# Power_Strip.net
KiCad netlist of a schematic drawn in EAGLE
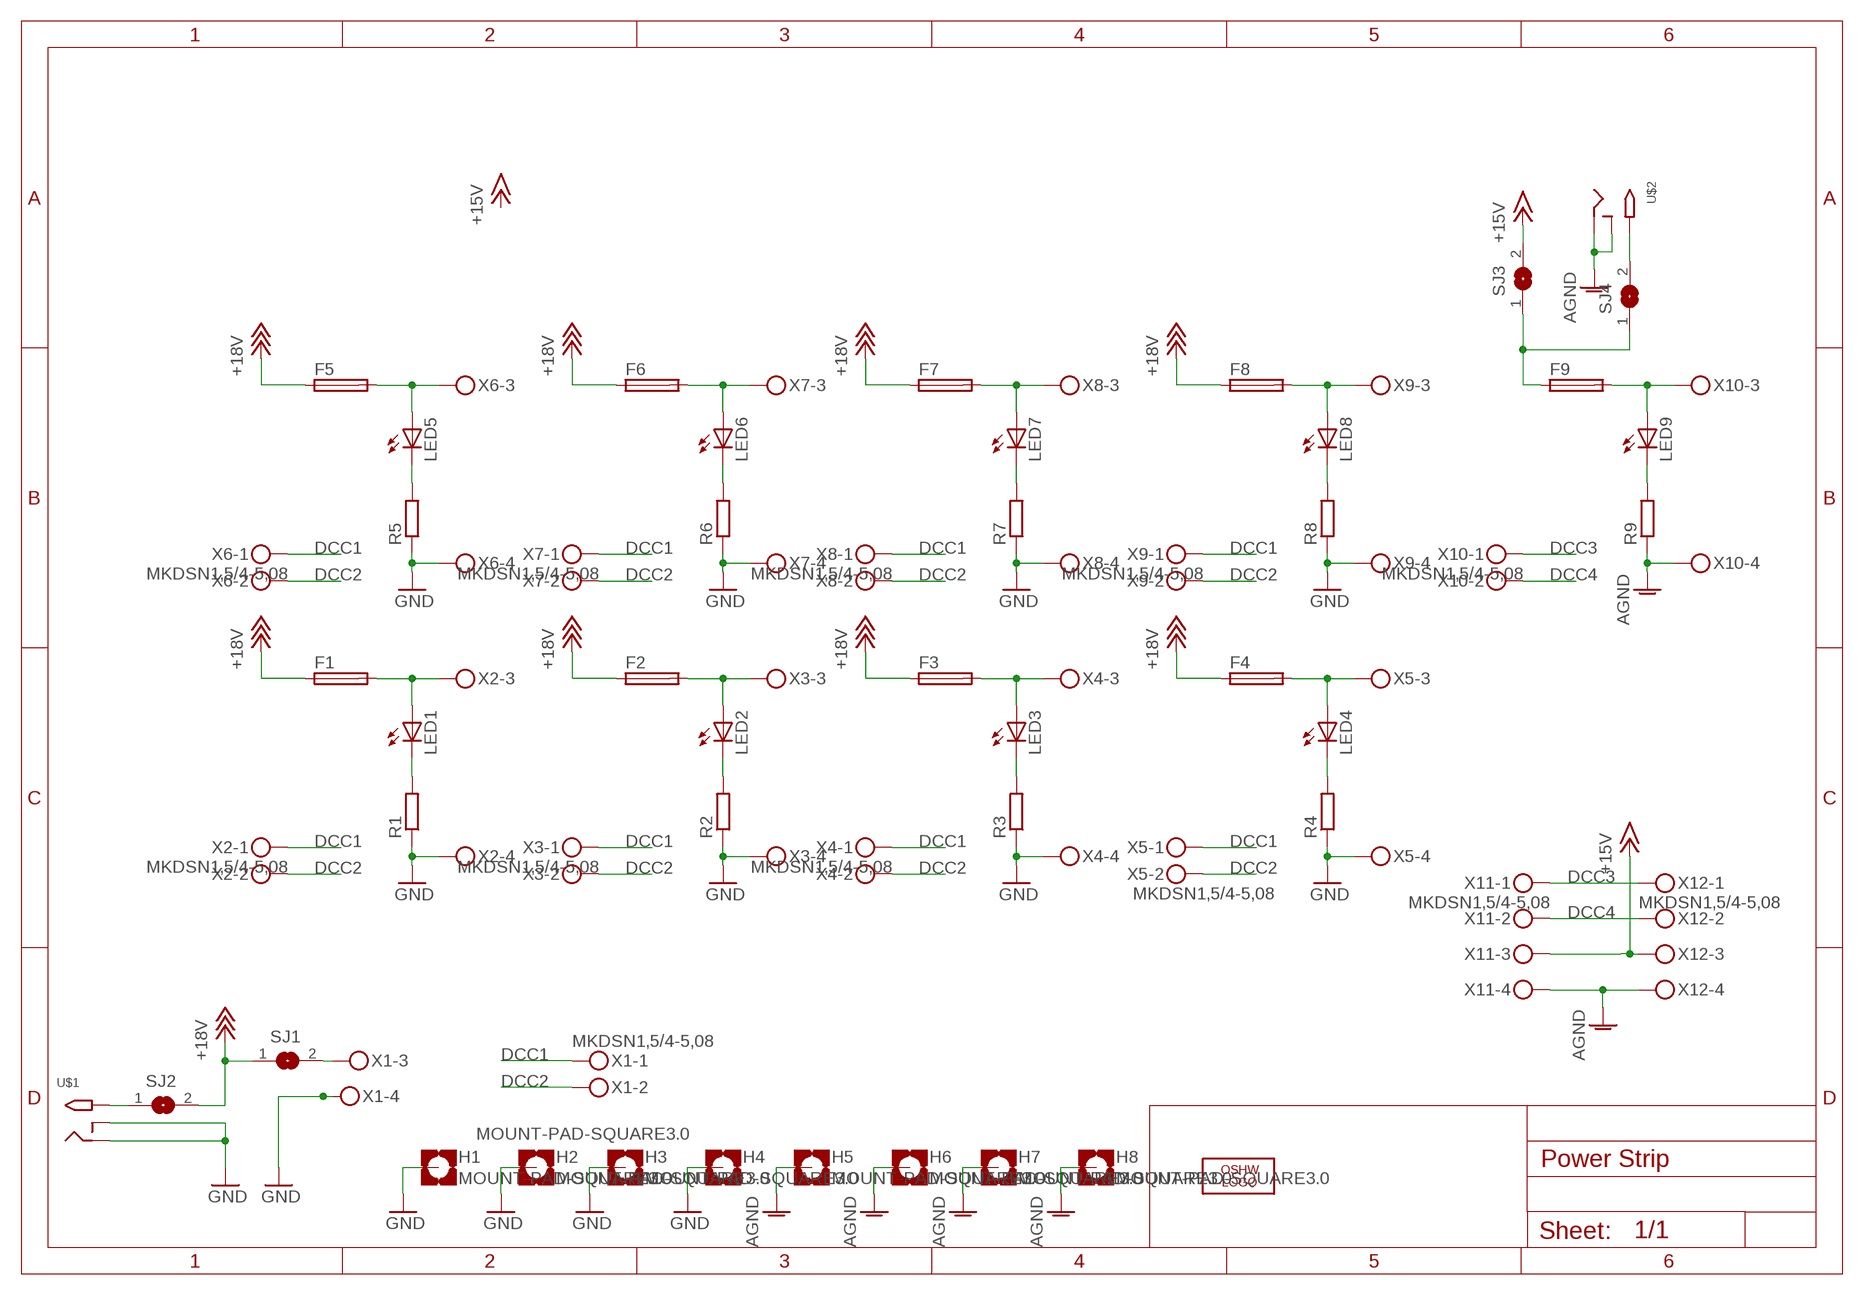
[diagram p0: schematic, sheet 1]

(export (version "E")
  (design (tool "Eeschema 10.0.6"))
  (components
    (comp (ref "F1")
      (value "TE5")
      (footprint "eagle-import:TE5")
      (libsource (lib "eagle-import") (part "TE5"))
    )
    (comp (ref "F2")
      (value "TE5")
      (footprint "eagle-import:TE5")
      (libsource (lib "eagle-import") (part "TE5"))
    )
    (comp (ref "F3")
      (value "TE5")
      (footprint "eagle-import:TE5")
      (libsource (lib "eagle-import") (part "TE5"))
    )
    (comp (ref "F4")
      (value "TE5")
      (footprint "eagle-import:TE5")
      (libsource (lib "eagle-import") (part "TE5"))
    )
    (comp (ref "F5")
      (value "TE5")
      (footprint "eagle-import:TE5")
      (libsource (lib "eagle-import") (part "TE5"))
    )
    (comp (ref "F6")
      (value "TE5")
      (footprint "eagle-import:TE5")
      (libsource (lib "eagle-import") (part "TE5"))
    )
    (comp (ref "F7")
      (value "TE5")
      (footprint "eagle-import:TE5")
      (libsource (lib "eagle-import") (part "TE5"))
    )
    (comp (ref "F8")
      (value "TE5")
      (footprint "eagle-import:TE5")
      (libsource (lib "eagle-import") (part "TE5"))
    )
    (comp (ref "F9")
      (value "TE5")
      (footprint "eagle-import:TE5")
      (libsource (lib "eagle-import") (part "TE5"))
    )
    (comp (ref "H1")
      (value "MOUNT-PAD-SQUARE3.0")
      (footprint "eagle-import:3,0-PAD-SQUARE")
      (libsource (lib "eagle-import") (part "MOUNT-PAD-SQUARE3.0"))
    )
    (comp (ref "H2")
      (value "MOUNT-PAD-SQUARE3.0")
      (footprint "eagle-import:3,0-PAD-SQUARE")
      (libsource (lib "eagle-import") (part "MOUNT-PAD-SQUARE3.0"))
    )
    (comp (ref "H3")
      (value "MOUNT-PAD-SQUARE3.0")
      (footprint "eagle-import:3,0-PAD-SQUARE")
      (libsource (lib "eagle-import") (part "MOUNT-PAD-SQUARE3.0"))
    )
    (comp (ref "H4")
      (value "MOUNT-PAD-SQUARE3.0")
      (footprint "eagle-import:3,0-PAD-SQUARE")
      (libsource (lib "eagle-import") (part "MOUNT-PAD-SQUARE3.0"))
    )
    (comp (ref "H5")
      (value "MOUNT-PAD-SQUARE3.0")
      (footprint "eagle-import:3,0-PAD-SQUARE")
      (libsource (lib "eagle-import") (part "MOUNT-PAD-SQUARE3.0"))
    )
    (comp (ref "H6")
      (value "MOUNT-PAD-SQUARE3.0")
      (footprint "eagle-import:3,0-PAD-SQUARE")
      (libsource (lib "eagle-import") (part "MOUNT-PAD-SQUARE3.0"))
    )
    (comp (ref "H7")
      (value "MOUNT-PAD-SQUARE3.0")
      (footprint "eagle-import:3,0-PAD-SQUARE")
      (libsource (lib "eagle-import") (part "MOUNT-PAD-SQUARE3.0"))
    )
    (comp (ref "H8")
      (value "MOUNT-PAD-SQUARE3.0")
      (footprint "eagle-import:3,0-PAD-SQUARE")
      (libsource (lib "eagle-import") (part "MOUNT-PAD-SQUARE3.0"))
    )
    (comp (ref "LED1")
      (value "LED3MM")
      (footprint "eagle-import:LED3MM")
      (libsource (lib "eagle-import") (part "LED3MM"))
    )
    (comp (ref "LED2")
      (value "LED3MM")
      (footprint "eagle-import:LED3MM")
      (libsource (lib "eagle-import") (part "LED3MM"))
    )
    (comp (ref "LED3")
      (value "LED3MM")
      (footprint "eagle-import:LED3MM")
      (libsource (lib "eagle-import") (part "LED3MM"))
    )
    (comp (ref "LED4")
      (value "LED3MM")
      (footprint "eagle-import:LED3MM")
      (libsource (lib "eagle-import") (part "LED3MM"))
    )
    (comp (ref "LED5")
      (value "LED3MM")
      (footprint "eagle-import:LED3MM")
      (libsource (lib "eagle-import") (part "LED3MM"))
    )
    (comp (ref "LED6")
      (value "LED3MM")
      (footprint "eagle-import:LED3MM")
      (libsource (lib "eagle-import") (part "LED3MM"))
    )
    (comp (ref "LED7")
      (value "LED3MM")
      (footprint "eagle-import:LED3MM")
      (libsource (lib "eagle-import") (part "LED3MM"))
    )
    (comp (ref "LED8")
      (value "LED3MM")
      (footprint "eagle-import:LED3MM")
      (libsource (lib "eagle-import") (part "LED3MM"))
    )
    (comp (ref "LED9")
      (value "LED3MM")
      (footprint "eagle-import:LED3MM")
      (libsource (lib "eagle-import") (part "LED3MM"))
    )
    (comp (ref "LOGO1")
      (value "OSHW_LOGO_6MILX0200-NT")
      (footprint "eagle-import:OSHW_6X200_NOTEXT")
      (libsource (lib "eagle-import") (part "OSHW_LOGO_6MILX0200-NT"))
    )
    (comp (ref "R1")
      (value "R-EU_R0805")
      (footprint "eagle-import:R0805")
      (libsource (lib "eagle-import") (part "R-EU_R0805"))
    )
    (comp (ref "R2")
      (value "R-EU_R0805")
      (footprint "eagle-import:R0805")
      (libsource (lib "eagle-import") (part "R-EU_R0805"))
    )
    (comp (ref "R3")
      (value "R-EU_R0805")
      (footprint "eagle-import:R0805")
      (libsource (lib "eagle-import") (part "R-EU_R0805"))
    )
    (comp (ref "R4")
      (value "R-EU_R0805")
      (footprint "eagle-import:R0805")
      (libsource (lib "eagle-import") (part "R-EU_R0805"))
    )
    (comp (ref "R5")
      (value "R-EU_R0805")
      (footprint "eagle-import:R0805")
      (libsource (lib "eagle-import") (part "R-EU_R0805"))
    )
    (comp (ref "R6")
      (value "R-EU_R0805")
      (footprint "eagle-import:R0805")
      (libsource (lib "eagle-import") (part "R-EU_R0805"))
    )
    (comp (ref "R7")
      (value "R-EU_R0805")
      (footprint "eagle-import:R0805")
      (libsource (lib "eagle-import") (part "R-EU_R0805"))
    )
    (comp (ref "R8")
      (value "R-EU_R0805")
      (footprint "eagle-import:R0805")
      (libsource (lib "eagle-import") (part "R-EU_R0805"))
    )
    (comp (ref "R9")
      (value "R-EU_R0805")
      (footprint "eagle-import:R0805")
      (libsource (lib "eagle-import") (part "R-EU_R0805"))
    )
    (comp (ref "SJ1") (value "SJ") (footprint "eagle-import:SJ") (libsource (lib "eagle-import") (part "SJ")))
    (comp (ref "SJ2") (value "SJ") (footprint "eagle-import:SJ") (libsource (lib "eagle-import") (part "SJ")))
    (comp (ref "SJ3") (value "SJ") (footprint "eagle-import:SJ") (libsource (lib "eagle-import") (part "SJ")))
    (comp (ref "SJ4") (value "SJ") (footprint "eagle-import:SJ") (libsource (lib "eagle-import") (part "SJ")))
    (comp (ref "U$1")
      (value "2.1MMJACKTHM")
      (footprint "eagle-import:PJ-102A")
      (libsource (lib "eagle-import") (part "2.1MMJACKTHM"))
    )
    (comp (ref "U$2")
      (value "2.1MMJACKTHM")
      (footprint "eagle-import:PJ-102A")
      (libsource (lib "eagle-import") (part "2.1MMJACKTHM"))
    )
    (comp (ref "X1")
      (value "MKDSN1,5/4-5,08")
      (footprint "eagle-import:MKDSN1,5_4-5,08")
      (libsource (lib "eagle-import") (part "MKDSN1,5/4-5,08"))
    )
    (comp (ref "X2")
      (value "MKDSN1,5/4-5,08")
      (footprint "eagle-import:MKDSN1,5_4-5,08")
      (libsource (lib "eagle-import") (part "MKDSN1,5/4-5,08"))
    )
    (comp (ref "X3")
      (value "MKDSN1,5/4-5,08")
      (footprint "eagle-import:MKDSN1,5_4-5,08")
      (libsource (lib "eagle-import") (part "MKDSN1,5/4-5,08"))
    )
    (comp (ref "X4")
      (value "MKDSN1,5/4-5,08")
      (footprint "eagle-import:MKDSN1,5_4-5,08")
      (libsource (lib "eagle-import") (part "MKDSN1,5/4-5,08"))
    )
    (comp (ref "X5")
      (value "MKDSN1,5/4-5,08")
      (footprint "eagle-import:MKDSN1,5_4-5,08")
      (libsource (lib "eagle-import") (part "MKDSN1,5/4-5,08"))
    )
    (comp (ref "X6")
      (value "MKDSN1,5/4-5,08")
      (footprint "eagle-import:MKDSN1,5_4-5,08")
      (libsource (lib "eagle-import") (part "MKDSN1,5/4-5,08"))
    )
    (comp (ref "X7")
      (value "MKDSN1,5/4-5,08")
      (footprint "eagle-import:MKDSN1,5_4-5,08")
      (libsource (lib "eagle-import") (part "MKDSN1,5/4-5,08"))
    )
    (comp (ref "X8")
      (value "MKDSN1,5/4-5,08")
      (footprint "eagle-import:MKDSN1,5_4-5,08")
      (libsource (lib "eagle-import") (part "MKDSN1,5/4-5,08"))
    )
    (comp (ref "X9")
      (value "MKDSN1,5/4-5,08")
      (footprint "eagle-import:MKDSN1,5_4-5,08")
      (libsource (lib "eagle-import") (part "MKDSN1,5/4-5,08"))
    )
    (comp (ref "X10")
      (value "MKDSN1,5/4-5,08")
      (footprint "eagle-import:MKDSN1,5_4-5,08")
      (libsource (lib "eagle-import") (part "MKDSN1,5/4-5,08"))
    )
    (comp (ref "X11")
      (value "MKDSN1,5/4-5,08")
      (footprint "eagle-import:MKDSN1,5_4-5,08")
      (libsource (lib "eagle-import") (part "MKDSN1,5/4-5,08"))
    )
    (comp (ref "X12")
      (value "MKDSN1,5/4-5,08")
      (footprint "eagle-import:MKDSN1,5_4-5,08")
      (libsource (lib "eagle-import") (part "MKDSN1,5/4-5,08"))
    )
  )
  (nets
    (net (code "1") (name "+15V") (class "Default")
      (node (ref "SJ3") (pin "2") (pinfunction "2_2") (pintype "passive"))
      (node (ref "X11") (pin "3") (pinfunction "KL_3") (pintype "passive"))
      (node (ref "X12") (pin "3") (pinfunction "KL_3") (pintype "passive"))
    )
    (net (code "2") (name "+18V") (class "Default")
      (node (ref "F1") (pin "1") (pinfunction "1_1") (pintype "passive"))
      (node (ref "F2") (pin "1") (pinfunction "1_1") (pintype "passive"))
      (node (ref "F3") (pin "1") (pinfunction "1_1") (pintype "passive"))
      (node (ref "F4") (pin "1") (pinfunction "1_1") (pintype "passive"))
      (node (ref "F5") (pin "1") (pinfunction "1_1") (pintype "passive"))
      (node (ref "F6") (pin "1") (pinfunction "1_1") (pintype "passive"))
      (node (ref "F7") (pin "1") (pinfunction "1_1") (pintype "passive"))
      (node (ref "F8") (pin "1") (pinfunction "1_1") (pintype "passive"))
      (node (ref "SJ1") (pin "1") (pinfunction "1_1") (pintype "passive"))
      (node (ref "SJ2") (pin "2") (pinfunction "2_2") (pintype "passive"))
    )
    (net (code "3") (name "/DCC1") (class "Default")
      (node (ref "X1") (pin "1") (pinfunction "KL_1") (pintype "passive"))
      (node (ref "X2") (pin "1") (pinfunction "KL_1") (pintype "passive"))
      (node (ref "X3") (pin "1") (pinfunction "KL_1") (pintype "passive"))
      (node (ref "X4") (pin "1") (pinfunction "KL_1") (pintype "passive"))
      (node (ref "X5") (pin "1") (pinfunction "KL_1") (pintype "passive"))
      (node (ref "X6") (pin "1") (pinfunction "KL_1") (pintype "passive"))
      (node (ref "X7") (pin "1") (pinfunction "KL_1") (pintype "passive"))
      (node (ref "X8") (pin "1") (pinfunction "KL_1") (pintype "passive"))
      (node (ref "X9") (pin "1") (pinfunction "KL_1") (pintype "passive"))
    )
    (net (code "4") (name "/DCC2") (class "Default")
      (node (ref "X1") (pin "2") (pinfunction "KL_2") (pintype "passive"))
      (node (ref "X2") (pin "2") (pinfunction "KL_2") (pintype "passive"))
      (node (ref "X3") (pin "2") (pinfunction "KL_2") (pintype "passive"))
      (node (ref "X4") (pin "2") (pinfunction "KL_2") (pintype "passive"))
      (node (ref "X5") (pin "2") (pinfunction "KL_2") (pintype "passive"))
      (node (ref "X6") (pin "2") (pinfunction "KL_2") (pintype "passive"))
      (node (ref "X7") (pin "2") (pinfunction "KL_2") (pintype "passive"))
      (node (ref "X8") (pin "2") (pinfunction "KL_2") (pintype "passive"))
      (node (ref "X9") (pin "2") (pinfunction "KL_2") (pintype "passive"))
    )
    (net (code "5") (name "/DCC3") (class "Default")
      (node (ref "X10") (pin "1") (pinfunction "KL_1") (pintype "passive"))
      (node (ref "X11") (pin "1") (pinfunction "KL_1") (pintype "passive"))
      (node (ref "X12") (pin "1") (pinfunction "KL_1") (pintype "passive"))
    )
    (net (code "6") (name "/DCC4") (class "Default")
      (node (ref "X10") (pin "2") (pinfunction "KL_2") (pintype "passive"))
      (node (ref "X11") (pin "2") (pinfunction "KL_2") (pintype "passive"))
      (node (ref "X12") (pin "2") (pinfunction "KL_2") (pintype "passive"))
    )
    (net (code "7") (name "AGND") (class "Default")
      (node (ref "H5") (pin "B3,0") (pinfunction "MOUNT_B3,0") (pintype "passive"))
      (node (ref "H6") (pin "B3,0") (pinfunction "MOUNT_B3,0") (pintype "passive"))
      (node (ref "H7") (pin "B3,0") (pinfunction "MOUNT_B3,0") (pintype "passive"))
      (node (ref "H8") (pin "B3,0") (pinfunction "MOUNT_B3,0") (pintype "passive"))
      (node (ref "R9") (pin "1") (pinfunction "1_1") (pintype "passive"))
      (node (ref "U$2") (pin "RING") (pinfunction "RING_RING") (pintype "bidirectional"))
      (node (ref "U$2") (pin "RING_SW") (pinfunction "RING_SW_RING_SW") (pintype "bidirectional"))
      (node (ref "X10") (pin "4") (pinfunction "KL_4") (pintype "passive"))
      (node (ref "X11") (pin "4") (pinfunction "KL_4") (pintype "passive"))
      (node (ref "X12") (pin "4") (pinfunction "KL_4") (pintype "passive"))
    )
    (net (code "8") (name "GND") (class "Default")
      (node (ref "H1") (pin "B3,0") (pinfunction "MOUNT_B3,0") (pintype "passive"))
      (node (ref "H2") (pin "B3,0") (pinfunction "MOUNT_B3,0") (pintype "passive"))
      (node (ref "H3") (pin "B3,0") (pinfunction "MOUNT_B3,0") (pintype "passive"))
      (node (ref "H4") (pin "B3,0") (pinfunction "MOUNT_B3,0") (pintype "passive"))
      (node (ref "R1") (pin "1") (pinfunction "1_1") (pintype "passive"))
      (node (ref "R2") (pin "1") (pinfunction "1_1") (pintype "passive"))
      (node (ref "R3") (pin "1") (pinfunction "1_1") (pintype "passive"))
      (node (ref "R4") (pin "1") (pinfunction "1_1") (pintype "passive"))
      (node (ref "R5") (pin "1") (pinfunction "1_1") (pintype "passive"))
      (node (ref "R6") (pin "1") (pinfunction "1_1") (pintype "passive"))
      (node (ref "R7") (pin "1") (pinfunction "1_1") (pintype "passive"))
      (node (ref "R8") (pin "1") (pinfunction "1_1") (pintype "passive"))
      (node (ref "U$1") (pin "RING") (pinfunction "RING_RING") (pintype "bidirectional"))
      (node (ref "U$1") (pin "RING_SW") (pinfunction "RING_SW_RING_SW") (pintype "bidirectional"))
      (node (ref "X1") (pin "4") (pinfunction "KL_4") (pintype "passive"))
      (node (ref "X2") (pin "4") (pinfunction "KL_4") (pintype "passive"))
      (node (ref "X3") (pin "4") (pinfunction "KL_4") (pintype "passive"))
      (node (ref "X4") (pin "4") (pinfunction "KL_4") (pintype "passive"))
      (node (ref "X5") (pin "4") (pinfunction "KL_4") (pintype "passive"))
      (node (ref "X6") (pin "4") (pinfunction "KL_4") (pintype "passive"))
      (node (ref "X7") (pin "4") (pinfunction "KL_4") (pintype "passive"))
      (node (ref "X8") (pin "4") (pinfunction "KL_4") (pintype "passive"))
      (node (ref "X9") (pin "4") (pinfunction "KL_4") (pintype "passive"))
    )
    (net (code "9") (name "Net-(F9-Pad1)") (class "Default")
      (node (ref "F9") (pin "1") (pinfunction "1_1") (pintype "passive"))
      (node (ref "SJ3") (pin "1") (pinfunction "1_1") (pintype "passive"))
      (node (ref "SJ4") (pin "1") (pinfunction "1_1") (pintype "passive"))
    )
    (net (code "10") (name "Net-(LED1-C)") (class "Default")
      (node (ref "LED1") (pin "K") (pinfunction "C_K") (pintype "passive"))
      (node (ref "R1") (pin "2") (pinfunction "2_2") (pintype "passive"))
    )
    (net (code "11") (name "Net-(LED2-C)") (class "Default")
      (node (ref "LED2") (pin "K") (pinfunction "C_K") (pintype "passive"))
      (node (ref "R2") (pin "2") (pinfunction "2_2") (pintype "passive"))
    )
    (net (code "12") (name "Net-(LED3-C)") (class "Default")
      (node (ref "LED3") (pin "K") (pinfunction "C_K") (pintype "passive"))
      (node (ref "R3") (pin "2") (pinfunction "2_2") (pintype "passive"))
    )
    (net (code "13") (name "Net-(LED4-C)") (class "Default")
      (node (ref "LED4") (pin "K") (pinfunction "C_K") (pintype "passive"))
      (node (ref "R4") (pin "2") (pinfunction "2_2") (pintype "passive"))
    )
    (net (code "14") (name "Net-(LED5-C)") (class "Default")
      (node (ref "LED5") (pin "K") (pinfunction "C_K") (pintype "passive"))
      (node (ref "R5") (pin "2") (pinfunction "2_2") (pintype "passive"))
    )
    (net (code "15") (name "Net-(LED6-C)") (class "Default")
      (node (ref "LED6") (pin "K") (pinfunction "C_K") (pintype "passive"))
      (node (ref "R6") (pin "2") (pinfunction "2_2") (pintype "passive"))
    )
    (net (code "16") (name "Net-(LED7-C)") (class "Default")
      (node (ref "LED7") (pin "K") (pinfunction "C_K") (pintype "passive"))
      (node (ref "R7") (pin "2") (pinfunction "2_2") (pintype "passive"))
    )
    (net (code "17") (name "Net-(LED8-C)") (class "Default")
      (node (ref "LED8") (pin "K") (pinfunction "C_K") (pintype "passive"))
      (node (ref "R8") (pin "2") (pinfunction "2_2") (pintype "passive"))
    )
    (net (code "18") (name "Net-(LED9-C)") (class "Default")
      (node (ref "LED9") (pin "K") (pinfunction "C_K") (pintype "passive"))
      (node (ref "R9") (pin "2") (pinfunction "2_2") (pintype "passive"))
    )
    (net (code "19") (name "Net-(SJ2-Pad1)") (class "Default")
      (node (ref "SJ2") (pin "1") (pinfunction "1_1") (pintype "passive"))
      (node (ref "U$1") (pin "TIP") (pinfunction "TIP_TIP") (pintype "bidirectional"))
    )
    (net (code "20") (name "Net-(SJ4-Pad2)") (class "Default")
      (node (ref "SJ4") (pin "2") (pinfunction "2_2") (pintype "passive"))
      (node (ref "U$2") (pin "TIP") (pinfunction "TIP_TIP") (pintype "bidirectional"))
    )
    (net (code "21") (name "Net-(X1C-KL)") (class "Default")
      (node (ref "SJ1") (pin "2") (pinfunction "2_2") (pintype "passive"))
      (node (ref "X1") (pin "3") (pinfunction "KL_3") (pintype "passive"))
    )
    (net (code "22") (name "Net-(X2C-KL)") (class "Default")
      (node (ref "F1") (pin "2") (pinfunction "2_2") (pintype "passive"))
      (node (ref "LED1") (pin "A") (pinfunction "A_A") (pintype "passive"))
      (node (ref "X2") (pin "3") (pinfunction "KL_3") (pintype "passive"))
    )
    (net (code "23") (name "Net-(X3C-KL)") (class "Default")
      (node (ref "F2") (pin "2") (pinfunction "2_2") (pintype "passive"))
      (node (ref "LED2") (pin "A") (pinfunction "A_A") (pintype "passive"))
      (node (ref "X3") (pin "3") (pinfunction "KL_3") (pintype "passive"))
    )
    (net (code "24") (name "Net-(X4C-KL)") (class "Default")
      (node (ref "F3") (pin "2") (pinfunction "2_2") (pintype "passive"))
      (node (ref "LED3") (pin "A") (pinfunction "A_A") (pintype "passive"))
      (node (ref "X4") (pin "3") (pinfunction "KL_3") (pintype "passive"))
    )
    (net (code "25") (name "Net-(X5C-KL)") (class "Default")
      (node (ref "F4") (pin "2") (pinfunction "2_2") (pintype "passive"))
      (node (ref "LED4") (pin "A") (pinfunction "A_A") (pintype "passive"))
      (node (ref "X5") (pin "3") (pinfunction "KL_3") (pintype "passive"))
    )
    (net (code "26") (name "Net-(X6C-KL)") (class "Default")
      (node (ref "F5") (pin "2") (pinfunction "2_2") (pintype "passive"))
      (node (ref "LED5") (pin "A") (pinfunction "A_A") (pintype "passive"))
      (node (ref "X6") (pin "3") (pinfunction "KL_3") (pintype "passive"))
    )
    (net (code "27") (name "Net-(X7C-KL)") (class "Default")
      (node (ref "F6") (pin "2") (pinfunction "2_2") (pintype "passive"))
      (node (ref "LED6") (pin "A") (pinfunction "A_A") (pintype "passive"))
      (node (ref "X7") (pin "3") (pinfunction "KL_3") (pintype "passive"))
    )
    (net (code "28") (name "Net-(X8C-KL)") (class "Default")
      (node (ref "F7") (pin "2") (pinfunction "2_2") (pintype "passive"))
      (node (ref "LED7") (pin "A") (pinfunction "A_A") (pintype "passive"))
      (node (ref "X8") (pin "3") (pinfunction "KL_3") (pintype "passive"))
    )
    (net (code "29") (name "Net-(X9C-KL)") (class "Default")
      (node (ref "F8") (pin "2") (pinfunction "2_2") (pintype "passive"))
      (node (ref "LED8") (pin "A") (pinfunction "A_A") (pintype "passive"))
      (node (ref "X9") (pin "3") (pinfunction "KL_3") (pintype "passive"))
    )
    (net (code "30") (name "Net-(X10C-KL)") (class "Default")
      (node (ref "F9") (pin "2") (pinfunction "2_2") (pintype "passive"))
      (node (ref "LED9") (pin "A") (pinfunction "A_A") (pintype "passive"))
      (node (ref "X10") (pin "3") (pinfunction "KL_3") (pintype "passive"))
    )
  )
)
